# W707L.net
KiCad netlist of a schematic drawn in EAGLE
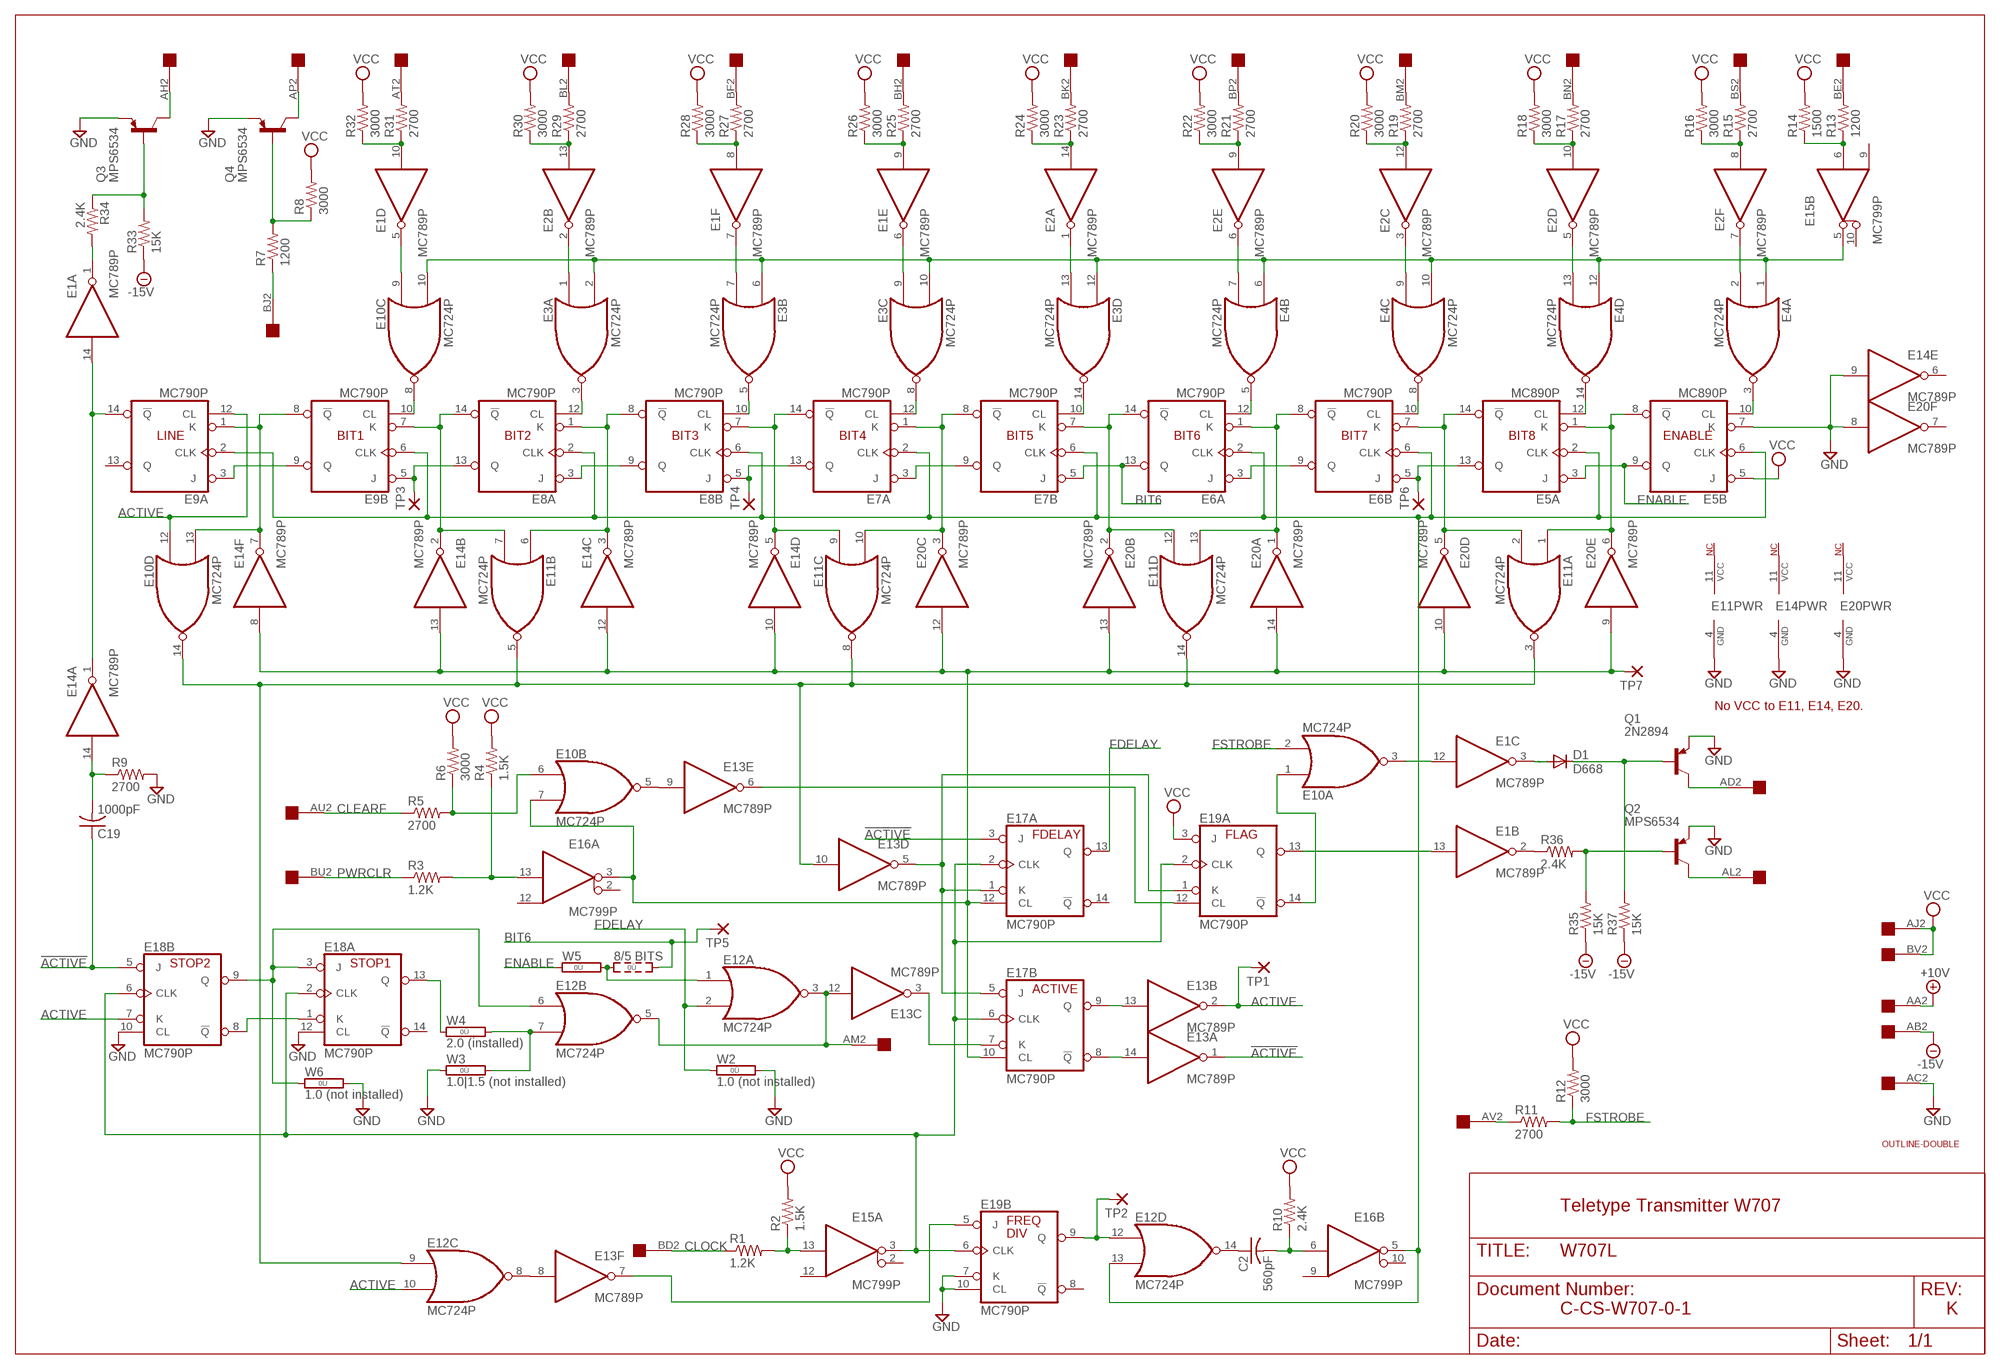
[diagram p0: schematic, sheet 1]

(export (version "E")
  (design (tool "Eeschema 10.0.6"))
  (components
    (comp (ref "C2")
      (value "560pF")
      (footprint "eagle-import:C050-025X075")
      (libsource (lib "eagle-import") (part "C-US050-025X075"))
    )
    (comp (ref "C19")
      (value "1000pF")
      (footprint "eagle-import:C050-025X075")
      (libsource (lib "eagle-import") (part "C-US050-025X075"))
    )
    (comp (ref "D1")
      (value "D668")
      (footprint "eagle-import:DO35-10")
      (libsource (lib "eagle-import") (part "1N4148DO35-10"))
    )
    (comp (ref "E1")
      (value "MC789P")
      (footprint "eagle-import:DIL14")
      (libsource (lib "eagle-import") (part "MC889P"))
    )
    (comp (ref "E2")
      (value "MC789P")
      (footprint "eagle-import:DIL14")
      (libsource (lib "eagle-import") (part "MC889P"))
    )
    (comp (ref "E3")
      (value "MC724P")
      (footprint "eagle-import:DIL14")
      (libsource (lib "eagle-import") (part "MC824P"))
    )
    (comp (ref "E4")
      (value "MC724P")
      (footprint "eagle-import:DIL14")
      (libsource (lib "eagle-import") (part "MC824P"))
    )
    (comp (ref "E5")
      (value "MC890P")
      (footprint "eagle-import:DIL14")
      (libsource (lib "eagle-import") (part "MC890P"))
    )
    (comp (ref "E6")
      (value "MC790P")
      (footprint "eagle-import:DIL14")
      (libsource (lib "eagle-import") (part "MC890P"))
    )
    (comp (ref "E7")
      (value "MC790P")
      (footprint "eagle-import:DIL14")
      (libsource (lib "eagle-import") (part "MC890P"))
    )
    (comp (ref "E8")
      (value "MC790P")
      (footprint "eagle-import:DIL14")
      (libsource (lib "eagle-import") (part "MC890P"))
    )
    (comp (ref "E9")
      (value "MC790P")
      (footprint "eagle-import:DIL14")
      (libsource (lib "eagle-import") (part "MC890P"))
    )
    (comp (ref "E10")
      (value "MC724P")
      (footprint "eagle-import:DIL14")
      (libsource (lib "eagle-import") (part "MC824P"))
    )
    (comp (ref "E11")
      (value "MC724P")
      (footprint "eagle-import:DIL14")
      (libsource (lib "eagle-import") (part "MC824P"))
    )
    (comp (ref "E12")
      (value "MC724P")
      (footprint "eagle-import:DIL14")
      (libsource (lib "eagle-import") (part "MC824P"))
    )
    (comp (ref "E13")
      (value "MC789P")
      (footprint "eagle-import:DIL14")
      (libsource (lib "eagle-import") (part "MC889P"))
    )
    (comp (ref "E14")
      (value "MC789P")
      (footprint "eagle-import:DIL14")
      (libsource (lib "eagle-import") (part "MC889P"))
    )
    (comp (ref "E15")
      (value "MC799P")
      (footprint "eagle-import:DIL14")
      (libsource (lib "eagle-import") (part "MC899P"))
    )
    (comp (ref "E16")
      (value "MC799P")
      (footprint "eagle-import:DIL14")
      (libsource (lib "eagle-import") (part "MC899P"))
    )
    (comp (ref "E17")
      (value "MC790P")
      (footprint "eagle-import:DIL14")
      (libsource (lib "eagle-import") (part "MC890P"))
    )
    (comp (ref "E18")
      (value "MC790P")
      (footprint "eagle-import:DIL14")
      (libsource (lib "eagle-import") (part "MC890P"))
    )
    (comp (ref "E19")
      (value "MC790P")
      (footprint "eagle-import:DIL14")
      (libsource (lib "eagle-import") (part "MC890P"))
    )
    (comp (ref "E20")
      (value "MC789P")
      (footprint "eagle-import:DIL14")
      (libsource (lib "eagle-import") (part "MC889P"))
    )
    (comp (ref "Q1")
      (value "2N2894")
      (footprint "eagle-import:TO39")
      (libsource (lib "eagle-import") (part "2N2904"))
    )
    (comp (ref "Q2")
      (value "MPS6534")
      (footprint "eagle-import:TO39")
      (libsource (lib "eagle-import") (part "2N2904"))
    )
    (comp (ref "Q3")
      (value "MPS6534")
      (footprint "eagle-import:TO39")
      (libsource (lib "eagle-import") (part "2N2904"))
    )
    (comp (ref "Q4")
      (value "MPS6534")
      (footprint "eagle-import:TO39")
      (libsource (lib "eagle-import") (part "2N2904"))
    )
    (comp (ref "R1")
      (value "1.2K")
      (footprint "eagle-import:0207_10")
      (libsource (lib "eagle-import") (part "R-US_0207/10"))
    )
    (comp (ref "R2")
      (value "1.5K")
      (footprint "eagle-import:0207_10")
      (libsource (lib "eagle-import") (part "R-US_0207/10"))
    )
    (comp (ref "R3")
      (value "1.2K")
      (footprint "eagle-import:0207_10")
      (libsource (lib "eagle-import") (part "R-US_0207/10"))
    )
    (comp (ref "R4")
      (value "1.5K")
      (footprint "eagle-import:0207_10")
      (libsource (lib "eagle-import") (part "R-US_0207/10"))
    )
    (comp (ref "R5")
      (value "2700")
      (footprint "eagle-import:0207_10")
      (libsource (lib "eagle-import") (part "R-US_0207/10"))
    )
    (comp (ref "R6")
      (value "3000")
      (footprint "eagle-import:0207_10")
      (libsource (lib "eagle-import") (part "R-US_0207/10"))
    )
    (comp (ref "R7")
      (value "1200")
      (footprint "eagle-import:0207_10")
      (libsource (lib "eagle-import") (part "R-US_0207/10"))
    )
    (comp (ref "R8")
      (value "3000")
      (footprint "eagle-import:0207_10")
      (libsource (lib "eagle-import") (part "R-US_0207/10"))
    )
    (comp (ref "R9")
      (value "2700")
      (footprint "eagle-import:0207_10")
      (libsource (lib "eagle-import") (part "R-US_0207/10"))
    )
    (comp (ref "R10")
      (value "2.4K")
      (footprint "eagle-import:0207_10")
      (libsource (lib "eagle-import") (part "R-US_0207/10"))
    )
    (comp (ref "R11")
      (value "2700")
      (footprint "eagle-import:0207_10")
      (libsource (lib "eagle-import") (part "R-US_0207/10"))
    )
    (comp (ref "R12")
      (value "3000")
      (footprint "eagle-import:0207_10")
      (libsource (lib "eagle-import") (part "R-US_0207/10"))
    )
    (comp (ref "R13")
      (value "1200")
      (footprint "eagle-import:0207_10")
      (libsource (lib "eagle-import") (part "R-US_0207/10"))
    )
    (comp (ref "R14")
      (value "1500")
      (footprint "eagle-import:0207_10")
      (libsource (lib "eagle-import") (part "R-US_0207/10"))
    )
    (comp (ref "R15")
      (value "2700")
      (footprint "eagle-import:0207_10")
      (libsource (lib "eagle-import") (part "R-US_0207/10"))
    )
    (comp (ref "R16")
      (value "3000")
      (footprint "eagle-import:0207_10")
      (libsource (lib "eagle-import") (part "R-US_0207/10"))
    )
    (comp (ref "R17")
      (value "2700")
      (footprint "eagle-import:0207_10")
      (libsource (lib "eagle-import") (part "R-US_0207/10"))
    )
    (comp (ref "R18")
      (value "3000")
      (footprint "eagle-import:0207_10")
      (libsource (lib "eagle-import") (part "R-US_0207/10"))
    )
    (comp (ref "R19")
      (value "2700")
      (footprint "eagle-import:0207_10")
      (libsource (lib "eagle-import") (part "R-US_0207/10"))
    )
    (comp (ref "R20")
      (value "3000")
      (footprint "eagle-import:0207_10")
      (libsource (lib "eagle-import") (part "R-US_0207/10"))
    )
    (comp (ref "R21")
      (value "2700")
      (footprint "eagle-import:0207_10")
      (libsource (lib "eagle-import") (part "R-US_0207/10"))
    )
    (comp (ref "R22")
      (value "3000")
      (footprint "eagle-import:0207_10")
      (libsource (lib "eagle-import") (part "R-US_0207/10"))
    )
    (comp (ref "R23")
      (value "2700")
      (footprint "eagle-import:0207_10")
      (libsource (lib "eagle-import") (part "R-US_0207/10"))
    )
    (comp (ref "R24")
      (value "3000")
      (footprint "eagle-import:0207_10")
      (libsource (lib "eagle-import") (part "R-US_0207/10"))
    )
    (comp (ref "R25")
      (value "2700")
      (footprint "eagle-import:0207_10")
      (libsource (lib "eagle-import") (part "R-US_0207/10"))
    )
    (comp (ref "R26")
      (value "3000")
      (footprint "eagle-import:0207_10")
      (libsource (lib "eagle-import") (part "R-US_0207/10"))
    )
    (comp (ref "R27")
      (value "2700")
      (footprint "eagle-import:0207_10")
      (libsource (lib "eagle-import") (part "R-US_0207/10"))
    )
    (comp (ref "R28")
      (value "3000")
      (footprint "eagle-import:0207_10")
      (libsource (lib "eagle-import") (part "R-US_0207/10"))
    )
    (comp (ref "R29")
      (value "2700")
      (footprint "eagle-import:0207_10")
      (libsource (lib "eagle-import") (part "R-US_0207/10"))
    )
    (comp (ref "R30")
      (value "3000")
      (footprint "eagle-import:0207_10")
      (libsource (lib "eagle-import") (part "R-US_0207/10"))
    )
    (comp (ref "R31")
      (value "2700")
      (footprint "eagle-import:0207_10")
      (libsource (lib "eagle-import") (part "R-US_0207/10"))
    )
    (comp (ref "R32")
      (value "3000")
      (footprint "eagle-import:0207_10")
      (libsource (lib "eagle-import") (part "R-US_0207/10"))
    )
    (comp (ref "R33")
      (value "15K")
      (footprint "eagle-import:0207_10")
      (libsource (lib "eagle-import") (part "R-US_0207/10"))
    )
    (comp (ref "R34")
      (value "2.4K")
      (footprint "eagle-import:0207_10")
      (libsource (lib "eagle-import") (part "R-US_0207/10"))
    )
    (comp (ref "R35")
      (value "15K")
      (footprint "eagle-import:0207_10")
      (libsource (lib "eagle-import") (part "R-US_0207/10"))
    )
    (comp (ref "R36")
      (value "2.4K")
      (footprint "eagle-import:0207_10")
      (libsource (lib "eagle-import") (part "R-US_0207/10"))
    )
    (comp (ref "R37")
      (value "15K")
      (footprint "eagle-import:0207_10")
      (libsource (lib "eagle-import") (part "R-US_0207/10"))
    )
    (comp (ref "TP1")
      (value "3,17/1,3")
      (footprint "eagle-import:3,17_1,3")
      (libsource (lib "eagle-import") (part "3,17/1,3"))
    )
    (comp (ref "TP2")
      (value "3,17/1,3")
      (footprint "eagle-import:3,17_1,3")
      (libsource (lib "eagle-import") (part "3,17/1,3"))
    )
    (comp (ref "TP3")
      (value "3,17/1,3")
      (footprint "eagle-import:3,17_1,3")
      (libsource (lib "eagle-import") (part "3,17/1,3"))
    )
    (comp (ref "TP4")
      (value "3,17/1,3")
      (footprint "eagle-import:3,17_1,3")
      (libsource (lib "eagle-import") (part "3,17/1,3"))
    )
    (comp (ref "TP5")
      (value "3,17/1,3")
      (footprint "eagle-import:3,17_1,3")
      (libsource (lib "eagle-import") (part "3,17/1,3"))
    )
    (comp (ref "TP6")
      (value "3,17/1,3")
      (footprint "eagle-import:3,17_1,3")
      (libsource (lib "eagle-import") (part "3,17/1,3"))
    )
    (comp (ref "TP7")
      (value "3,17/1,3")
      (footprint "eagle-import:3,17_1,3")
      (libsource (lib "eagle-import") (part "3,17/1,3"))
    )
    (comp (ref "U$1")
      (value "OUTLINE-DOUBLE")
      (footprint "eagle-import:DOUBLE")
      (libsource (lib "eagle-import") (part "OUTLINE-DOUBLE"))
    )
    (comp (ref "U$2")
      (value "DOUBLE")
      (footprint "eagle-import:EDGE-CON4")
      (libsource (lib "eagle-import") (part "DOUBLE"))
    )
    (comp (ref "W2")
      (value "1.0 (not installed)")
      (footprint "eagle-import:0R_10")
      (libsource (lib "eagle-import") (part "0R"))
    )
    (comp (ref "W3")
      (value "1.0|1.5 (not installed)")
      (footprint "eagle-import:0R_10")
      (libsource (lib "eagle-import") (part "0R"))
    )
    (comp (ref "W4")
      (value "2.0 (installed)")
      (footprint "eagle-import:0R_10")
      (libsource (lib "eagle-import") (part "0R"))
    )
    (comp (ref "W5")
      (value "8/5 BITS")
      (footprint "eagle-import:0R2_10")
      (libsource (lib "eagle-import") (part "0R2"))
    )
    (comp (ref "W6")
      (value "1.0 (not installed)")
      (footprint "eagle-import:0R_10")
      (libsource (lib "eagle-import") (part "0R"))
    )
  )
  (nets
    (net (code "1") (name "+10V") (class "Default")
      (node (ref "U$2") (pin "AA2") (pinfunction "1_AA2") (pintype "bidirectional"))
    )
    (net (code "2") (name "-15V") (class "Default")
      (node (ref "R33") (pin "1") (pinfunction "1_1") (pintype "passive"))
      (node (ref "R35") (pin "1") (pinfunction "1_1") (pintype "passive"))
      (node (ref "R37") (pin "1") (pinfunction "1_1") (pintype "passive"))
      (node (ref "U$2") (pin "AB2") (pinfunction "1_AB2") (pintype "bidirectional"))
    )
    (net (code "3") (name "/ACTIVE") (class "Default")
      (node (ref "E10") (pin "12") (pinfunction "I0_12") (pintype "input"))
      (node (ref "E12") (pin "10") (pinfunction "I1_10") (pintype "input"))
      (node (ref "E13") (pin "2") (pinfunction "O_2") (pintype "output"))
      (node (ref "E18") (pin "7") (pinfunction "K_7") (pintype "input"))
      (node (ref "E9") (pin "12") (pinfunction "CL_12") (pintype "input"))
      (node (ref "TP1") (pin "1") (pinfunction "P_1") (pintype "passive"))
    )
    (net (code "4") (name "/BIT6") (class "Default")
      (node (ref "E6") (pin "13") (pinfunction "Q_13") (pintype "output"))
      (node (ref "E7") (pin "5") (pinfunction "J_5") (pintype "input"))
      (node (ref "TP5") (pin "1") (pinfunction "P_1") (pintype "passive"))
      (node (ref "W5") (pin "3") (pinfunction "3_3") (pintype "passive"))
    )
    (net (code "5") (name "/CLEARF") (class "Default")
      (node (ref "R5") (pin "1") (pinfunction "1_1") (pintype "passive"))
      (node (ref "U$2") (pin "AU2") (pinfunction "1_AU2") (pintype "bidirectional"))
    )
    (net (code "6") (name "/CLOCK") (class "Default")
      (node (ref "R1") (pin "1") (pinfunction "1_1") (pintype "passive"))
      (node (ref "U$2") (pin "BD2") (pinfunction "1_BD2") (pintype "bidirectional"))
    )
    (net (code "7") (name "/ENABLE") (class "Default")
      (node (ref "E5") (pin "3") (pinfunction "J_3") (pintype "input"))
      (node (ref "E5") (pin "9") (pinfunction "Q_9") (pintype "output"))
      (node (ref "W5") (pin "1") (pinfunction "1_1") (pintype "passive"))
    )
    (net (code "8") (name "/FDELAY") (class "Default")
      (node (ref "E12") (pin "2") (pinfunction "I1_2") (pintype "input"))
      (node (ref "E17") (pin "13") (pinfunction "Q_13") (pintype "output"))
      (node (ref "W2") (pin "1") (pinfunction "1_1") (pintype "passive"))
    )
    (net (code "9") (name "/FSTROBE") (class "Default")
      (node (ref "E10") (pin "2") (pinfunction "I1_2") (pintype "input"))
      (node (ref "R11") (pin "2") (pinfunction "2_2") (pintype "passive"))
      (node (ref "R12") (pin "1") (pinfunction "1_1") (pintype "passive"))
    )
    (net (code "10") (name "/PWRCLR") (class "Default")
      (node (ref "R3") (pin "1") (pinfunction "1_1") (pintype "passive"))
      (node (ref "U$2") (pin "BU2") (pinfunction "1_BU2") (pintype "bidirectional"))
    )
    (net (code "11") (name "/~{ACTIVE}") (class "Default")
      (node (ref "C19") (pin "1") (pinfunction "1_1") (pintype "passive"))
      (node (ref "E13") (pin "1") (pinfunction "O_1") (pintype "output"))
      (node (ref "E17") (pin "3") (pinfunction "J_3") (pintype "input"))
      (node (ref "E18") (pin "5") (pinfunction "J_5") (pintype "input"))
    )
    (net (code "12") (name "GND") (class "Default")
      (node (ref "E11") (pin "4") (pinfunction "GND_4") (pintype "power_in"))
      (node (ref "E14") (pin "4") (pinfunction "GND_4") (pintype "power_in"))
      (node (ref "E14") (pin "9") (pinfunction "I_9") (pintype "input"))
      (node (ref "E18") (pin "10") (pinfunction "CL_10") (pintype "input"))
      (node (ref "E18") (pin "12") (pinfunction "CL_12") (pintype "input"))
      (node (ref "E19") (pin "10") (pinfunction "CL_10") (pintype "input"))
      (node (ref "E19") (pin "7") (pinfunction "K_7") (pintype "input"))
      (node (ref "E20") (pin "4") (pinfunction "GND_4") (pintype "power_in"))
      (node (ref "E20") (pin "8") (pinfunction "I_8") (pintype "input"))
      (node (ref "E5") (pin "7") (pinfunction "K_7") (pintype "input"))
      (node (ref "Q1") (pin "1") (pinfunction "E_1") (pintype "passive"))
      (node (ref "Q2") (pin "1") (pinfunction "E_1") (pintype "passive"))
      (node (ref "Q3") (pin "1") (pinfunction "E_1") (pintype "passive"))
      (node (ref "Q4") (pin "1") (pinfunction "E_1") (pintype "passive"))
      (node (ref "R9") (pin "2") (pinfunction "2_2") (pintype "passive"))
      (node (ref "U$2") (pin "AC2") (pinfunction "1_AC2") (pintype "bidirectional"))
      (node (ref "W2") (pin "2") (pinfunction "2_2") (pintype "passive"))
      (node (ref "W3") (pin "1") (pinfunction "1_1") (pintype "passive"))
      (node (ref "W6") (pin "2") (pinfunction "2_2") (pintype "passive"))
    )
    (net (code "13") (name "NC") (class "Default")
      (node (ref "E11") (pin "11") (pinfunction "VCC_11") (pintype "power_in"))
      (node (ref "E14") (pin "11") (pinfunction "VCC_11") (pintype "power_in"))
      (node (ref "E20") (pin "11") (pinfunction "VCC_11") (pintype "power_in"))
    )
    (net (code "14") (name "Net-(E1A-O)") (class "Default")
      (node (ref "E1") (pin "1") (pinfunction "O_1") (pintype "output"))
      (node (ref "R34") (pin "2") (pinfunction "2_2") (pintype "passive"))
    )
    (net (code "15") (name "Net-(E1B-O)") (class "Default")
      (node (ref "E1") (pin "2") (pinfunction "O_2") (pintype "output"))
      (node (ref "R36") (pin "1") (pinfunction "1_1") (pintype "passive"))
    )
    (net (code "16") (name "Net-(E1C-O)") (class "Default")
      (node (ref "D1") (pin "A") (pinfunction "A_A") (pintype "passive"))
      (node (ref "E1") (pin "3") (pinfunction "O_3") (pintype "output"))
    )
    (net (code "17") (name "Net-(E1D-I)") (class "Default")
      (node (ref "E1") (pin "10") (pinfunction "I_10") (pintype "input"))
      (node (ref "R31") (pin "1") (pinfunction "1_1") (pintype "passive"))
      (node (ref "R32") (pin "1") (pinfunction "1_1") (pintype "passive"))
    )
    (net (code "18") (name "Net-(E1E-I)") (class "Default")
      (node (ref "E1") (pin "9") (pinfunction "I_9") (pintype "input"))
      (node (ref "R25") (pin "1") (pinfunction "1_1") (pintype "passive"))
      (node (ref "R26") (pin "1") (pinfunction "1_1") (pintype "passive"))
    )
    (net (code "19") (name "Net-(E1E-O)") (class "Default")
      (node (ref "E1") (pin "6") (pinfunction "O_6") (pintype "output"))
      (node (ref "E3") (pin "9") (pinfunction "I0_9") (pintype "input"))
    )
    (net (code "20") (name "Net-(E1F-I)") (class "Default")
      (node (ref "E1") (pin "8") (pinfunction "I_8") (pintype "input"))
      (node (ref "R27") (pin "1") (pinfunction "1_1") (pintype "passive"))
      (node (ref "R28") (pin "1") (pinfunction "1_1") (pintype "passive"))
    )
    (net (code "21") (name "Net-(E1F-O)") (class "Default")
      (node (ref "E1") (pin "7") (pinfunction "O_7") (pintype "output"))
      (node (ref "E3") (pin "7") (pinfunction "I1_7") (pintype "input"))
    )
    (net (code "22") (name "Net-(E2A-I)") (class "Default")
      (node (ref "E2") (pin "14") (pinfunction "I_14") (pintype "input"))
      (node (ref "R23") (pin "1") (pinfunction "1_1") (pintype "passive"))
      (node (ref "R24") (pin "1") (pinfunction "1_1") (pintype "passive"))
    )
    (net (code "23") (name "Net-(E2A-O)") (class "Default")
      (node (ref "E2") (pin "1") (pinfunction "O_1") (pintype "output"))
      (node (ref "E3") (pin "13") (pinfunction "I1_13") (pintype "input"))
    )
    (net (code "24") (name "Net-(E2B-I)") (class "Default")
      (node (ref "E2") (pin "13") (pinfunction "I_13") (pintype "input"))
      (node (ref "R29") (pin "1") (pinfunction "1_1") (pintype "passive"))
      (node (ref "R30") (pin "1") (pinfunction "1_1") (pintype "passive"))
    )
    (net (code "25") (name "Net-(E2B-O)") (class "Default")
      (node (ref "E2") (pin "2") (pinfunction "O_2") (pintype "output"))
      (node (ref "E3") (pin "1") (pinfunction "I0_1") (pintype "input"))
    )
    (net (code "26") (name "Net-(E2C-I)") (class "Default")
      (node (ref "E2") (pin "12") (pinfunction "I_12") (pintype "input"))
      (node (ref "R19") (pin "1") (pinfunction "1_1") (pintype "passive"))
      (node (ref "R20") (pin "1") (pinfunction "1_1") (pintype "passive"))
    )
    (net (code "27") (name "Net-(E2C-O)") (class "Default")
      (node (ref "E2") (pin "3") (pinfunction "O_3") (pintype "output"))
      (node (ref "E4") (pin "9") (pinfunction "I0_9") (pintype "input"))
    )
    (net (code "28") (name "Net-(E2D-I)") (class "Default")
      (node (ref "E2") (pin "10") (pinfunction "I_10") (pintype "input"))
      (node (ref "R17") (pin "1") (pinfunction "1_1") (pintype "passive"))
      (node (ref "R18") (pin "1") (pinfunction "1_1") (pintype "passive"))
    )
    (net (code "29") (name "Net-(E2D-O)") (class "Default")
      (node (ref "E2") (pin "5") (pinfunction "O_5") (pintype "output"))
      (node (ref "E4") (pin "13") (pinfunction "I1_13") (pintype "input"))
    )
    (net (code "30") (name "Net-(E2E-I)") (class "Default")
      (node (ref "E2") (pin "9") (pinfunction "I_9") (pintype "input"))
      (node (ref "R21") (pin "1") (pinfunction "1_1") (pintype "passive"))
      (node (ref "R22") (pin "1") (pinfunction "1_1") (pintype "passive"))
    )
    (net (code "31") (name "Net-(E2E-O)") (class "Default")
      (node (ref "E2") (pin "6") (pinfunction "O_6") (pintype "output"))
      (node (ref "E4") (pin "7") (pinfunction "I1_7") (pintype "input"))
    )
    (net (code "32") (name "Net-(E2F-I)") (class "Default")
      (node (ref "E2") (pin "8") (pinfunction "I_8") (pintype "input"))
      (node (ref "R15") (pin "1") (pinfunction "1_1") (pintype "passive"))
      (node (ref "R16") (pin "1") (pinfunction "1_1") (pintype "passive"))
    )
    (net (code "33") (name "Net-(E2F-O)") (class "Default")
      (node (ref "E2") (pin "7") (pinfunction "O_7") (pintype "output"))
      (node (ref "E4") (pin "2") (pinfunction "I1_2") (pintype "input"))
    )
    (net (code "34") (name "Net-(E3A-O)") (class "Default")
      (node (ref "E3") (pin "3") (pinfunction "O_3") (pintype "output"))
      (node (ref "E8") (pin "12") (pinfunction "CL_12") (pintype "input"))
    )
    (net (code "35") (name "Net-(E3B-O)") (class "Default")
      (node (ref "E3") (pin "5") (pinfunction "O_5") (pintype "output"))
      (node (ref "E8") (pin "10") (pinfunction "CL_10") (pintype "input"))
    )
    (net (code "36") (name "Net-(E3C-O)") (class "Default")
      (node (ref "E3") (pin "8") (pinfunction "O_8") (pintype "output"))
      (node (ref "E7") (pin "12") (pinfunction "CL_12") (pintype "input"))
    )
    (net (code "37") (name "Net-(E3D-O)") (class "Default")
      (node (ref "E3") (pin "14") (pinfunction "O_14") (pintype "output"))
      (node (ref "E7") (pin "10") (pinfunction "CL_10") (pintype "input"))
    )
    (net (code "38") (name "Net-(E4A-O)") (class "Default")
      (node (ref "E4") (pin "3") (pinfunction "O_3") (pintype "output"))
      (node (ref "E5") (pin "10") (pinfunction "CL_10") (pintype "input"))
    )
    (net (code "39") (name "Net-(E4B-O)") (class "Default")
      (node (ref "E4") (pin "5") (pinfunction "O_5") (pintype "output"))
      (node (ref "E6") (pin "12") (pinfunction "CL_12") (pintype "input"))
    )
    (net (code "40") (name "Net-(E4C-O)") (class "Default")
      (node (ref "E4") (pin "8") (pinfunction "O_8") (pintype "output"))
      (node (ref "E6") (pin "10") (pinfunction "CL_10") (pintype "input"))
    )
    (net (code "41") (name "Net-(E4D-O)") (class "Default")
      (node (ref "E4") (pin "14") (pinfunction "O_14") (pintype "output"))
      (node (ref "E5") (pin "12") (pinfunction "CL_12") (pintype "input"))
    )
    (net (code "42") (name "Net-(E5A-Q)") (class "Default")
      (node (ref "E5") (pin "13") (pinfunction "Q_13") (pintype "output"))
      (node (ref "E6") (pin "5") (pinfunction "J_5") (pintype "input"))
      (node (ref "TP6") (pin "1") (pinfunction "P_1") (pintype "passive"))
    )
    (net (code "43") (name "Net-(E6A-J)") (class "Default")
      (node (ref "E6") (pin "3") (pinfunction "J_3") (pintype "input"))
      (node (ref "E6") (pin "9") (pinfunction "Q_9") (pintype "output"))
    )
    (net (code "44") (name "Net-(E7A-J)") (class "Default")
      (node (ref "E7") (pin "3") (pinfunction "J_3") (pintype "input"))
      (node (ref "E7") (pin "9") (pinfunction "Q_9") (pintype "output"))
    )
    (net (code "45") (name "Net-(E7A-Q)") (class "Default")
      (node (ref "E7") (pin "13") (pinfunction "Q_13") (pintype "output"))
      (node (ref "E8") (pin "5") (pinfunction "J_5") (pintype "input"))
      (node (ref "TP4") (pin "1") (pinfunction "P_1") (pintype "passive"))
    )
    (net (code "46") (name "Net-(E8A-J)") (class "Default")
      (node (ref "E8") (pin "3") (pinfunction "J_3") (pintype "input"))
      (node (ref "E8") (pin "9") (pinfunction "Q_9") (pintype "output"))
    )
    (net (code "47") (name "Net-(E8A-Q)") (class "Default")
      (node (ref "E8") (pin "13") (pinfunction "Q_13") (pintype "output"))
      (node (ref "E9") (pin "5") (pinfunction "J_5") (pintype "input"))
      (node (ref "TP3") (pin "1") (pinfunction "P_1") (pintype "passive"))
    )
    (net (code "48") (name "Net-(E9A-J)") (class "Default")
      (node (ref "E9") (pin "3") (pinfunction "J_3") (pintype "input"))
      (node (ref "E9") (pin "9") (pinfunction "Q_9") (pintype "output"))
    )
    (net (code "49") (name "Net-(E10A-I0)") (class "Default")
      (node (ref "E10") (pin "1") (pinfunction "I0_1") (pintype "input"))
      (node (ref "E19") (pin "14") (pinfunction "~{Q}_14") (pintype "output"))
    )
    (net (code "50") (name "Net-(E10A-O)") (class "Default")
      (node (ref "E1") (pin "12") (pinfunction "I_12") (pintype "input"))
      (node (ref "E10") (pin "3") (pinfunction "O_3") (pintype "output"))
    )
    (net (code "51") (name "Net-(E10B-I0)") (class "Default")
      (node (ref "E10") (pin "6") (pinfunction "I0_6") (pintype "input"))
      (node (ref "R5") (pin "2") (pinfunction "2_2") (pintype "passive"))
      (node (ref "R6") (pin "1") (pinfunction "1_1") (pintype "passive"))
    )
    (net (code "52") (name "Net-(E10B-I1)") (class "Default")
      (node (ref "E10") (pin "7") (pinfunction "I1_7") (pintype "input"))
      (node (ref "E14") (pin "10") (pinfunction "I_10") (pintype "input"))
      (node (ref "E14") (pin "12") (pinfunction "I_12") (pintype "input"))
      (node (ref "E14") (pin "13") (pinfunction "I_13") (pintype "input"))
      (node (ref "E14") (pin "8") (pinfunction "I_8") (pintype "input"))
      (node (ref "E16") (pin "3") (pinfunction "O_3") (pintype "output"))
      (node (ref "E17") (pin "10") (pinfunction "CL_10") (pintype "input"))
      (node (ref "E17") (pin "12") (pinfunction "CL_12") (pintype "input"))
      (node (ref "E20") (pin "10") (pinfunction "I_10") (pintype "input"))
      (node (ref "E20") (pin "12") (pinfunction "I_12") (pintype "input"))
      (node (ref "E20") (pin "13") (pinfunction "I_13") (pintype "input"))
      (node (ref "E20") (pin "14") (pinfunction "I_14") (pintype "input"))
      (node (ref "E20") (pin "9") (pinfunction "I_9") (pintype "input"))
      (node (ref "TP7") (pin "1") (pinfunction "P_1") (pintype "passive"))
    )
    (net (code "53") (name "Net-(E10B-O)") (class "Default")
      (node (ref "E10") (pin "5") (pinfunction "O_5") (pintype "output"))
      (node (ref "E13") (pin "9") (pinfunction "I_9") (pintype "input"))
    )
    (net (code "54") (name "Net-(E10C-I0)") (class "Default")
      (node (ref "E1") (pin "5") (pinfunction "O_5") (pintype "output"))
      (node (ref "E10") (pin "9") (pinfunction "I0_9") (pintype "input"))
    )
    (net (code "55") (name "Net-(E10C-I1)") (class "Default")
      (node (ref "E10") (pin "10") (pinfunction "I1_10") (pintype "input"))
      (node (ref "E15") (pin "5") (pinfunction "O_5") (pintype "output"))
      (node (ref "E3") (pin "10") (pinfunction "I1_10") (pintype "input"))
      (node (ref "E3") (pin "12") (pinfunction "I0_12") (pintype "input"))
      (node (ref "E3") (pin "2") (pinfunction "I1_2") (pintype "input"))
      (node (ref "E3") (pin "6") (pinfunction "I0_6") (pintype "input"))
      (node (ref "E4") (pin "1") (pinfunction "I0_1") (pintype "input"))
      (node (ref "E4") (pin "10") (pinfunction "I1_10") (pintype "input"))
      (node (ref "E4") (pin "12") (pinfunction "I0_12") (pintype "input"))
      (node (ref "E4") (pin "6") (pinfunction "I0_6") (pintype "input"))
    )
    (net (code "56") (name "Net-(E10C-O)") (class "Default")
      (node (ref "E10") (pin "8") (pinfunction "O_8") (pintype "output"))
      (node (ref "E9") (pin "10") (pinfunction "CL_10") (pintype "input"))
    )
    (net (code "57") (name "Net-(E10D-I1)") (class "Default")
      (node (ref "E10") (pin "13") (pinfunction "I1_13") (pintype "input"))
      (node (ref "E14") (pin "7") (pinfunction "O_7") (pintype "output"))
      (node (ref "E9") (pin "1") (pinfunction "K_1") (pintype "input"))
      (node (ref "E9") (pin "8") (pinfunction "~{Q}_8") (pintype "output"))
    )
    (net (code "58") (name "Net-(E10D-O)") (class "Default")
      (node (ref "E10") (pin "14") (pinfunction "O_14") (pintype "output"))
      (node (ref "E11") (pin "14") (pinfunction "O_14") (pintype "output"))
      (node (ref "E11") (pin "3") (pinfunction "O_3") (pintype "output"))
      (node (ref "E11") (pin "5") (pinfunction "O_5") (pintype "output"))
      (node (ref "E11") (pin "8") (pinfunction "O_8") (pintype "output"))
      (node (ref "E12") (pin "9") (pinfunction "I0_9") (pintype "input"))
      (node (ref "E13") (pin "10") (pinfunction "I_10") (pintype "input"))
    )
    (net (code "59") (name "Net-(E11A-I0)") (class "Default")
      (node (ref "E11") (pin "1") (pinfunction "I0_1") (pintype "input"))
      (node (ref "E20") (pin "6") (pinfunction "O_6") (pintype "output"))
      (node (ref "E5") (pin "1") (pinfunction "K_1") (pintype "input"))
      (node (ref "E5") (pin "8") (pinfunction "~{Q}_8") (pintype "output"))
    )
    (net (code "60") (name "Net-(E11A-I1)") (class "Default")
      (node (ref "E11") (pin "2") (pinfunction "I1_2") (pintype "input"))
      (node (ref "E20") (pin "5") (pinfunction "O_5") (pintype "output"))
      (node (ref "E5") (pin "14") (pinfunction "~{Q}_14") (pintype "output"))
      (node (ref "E6") (pin "7") (pinfunction "K_7") (pintype "input"))
    )
    (net (code "61") (name "Net-(E11B-I0)") (class "Default")
      (node (ref "E11") (pin "6") (pinfunction "I0_6") (pintype "input"))
      (node (ref "E14") (pin "3") (pinfunction "O_3") (pintype "output"))
      (node (ref "E8") (pin "1") (pinfunction "K_1") (pintype "input"))
      (node (ref "E8") (pin "8") (pinfunction "~{Q}_8") (pintype "output"))
    )
    (net (code "62") (name "Net-(E11B-I1)") (class "Default")
      (node (ref "E11") (pin "7") (pinfunction "I1_7") (pintype "input"))
      (node (ref "E14") (pin "2") (pinfunction "O_2") (pintype "output"))
      (node (ref "E8") (pin "14") (pinfunction "~{Q}_14") (pintype "output"))
      (node (ref "E9") (pin "7") (pinfunction "K_7") (pintype "input"))
    )
    (net (code "63") (name "Net-(E11C-I0)") (class "Default")
      (node (ref "E11") (pin "9") (pinfunction "I0_9") (pintype "input"))
      (node (ref "E14") (pin "5") (pinfunction "O_5") (pintype "output"))
      (node (ref "E7") (pin "14") (pinfunction "~{Q}_14") (pintype "output"))
      (node (ref "E8") (pin "7") (pinfunction "K_7") (pintype "input"))
    )
    (net (code "64") (name "Net-(E11C-I1)") (class "Default")
      (node (ref "E11") (pin "10") (pinfunction "I1_10") (pintype "input"))
      (node (ref "E20") (pin "3") (pinfunction "O_3") (pintype "output"))
      (node (ref "E7") (pin "1") (pinfunction "K_1") (pintype "input"))
      (node (ref "E7") (pin "8") (pinfunction "~{Q}_8") (pintype "output"))
    )
    (net (code "65") (name "Net-(E11D-I0)") (class "Default")
      (node (ref "E11") (pin "12") (pinfunction "I0_12") (pintype "input"))
      (node (ref "E20") (pin "2") (pinfunction "O_2") (pintype "output"))
      (node (ref "E6") (pin "14") (pinfunction "~{Q}_14") (pintype "output"))
      (node (ref "E7") (pin "7") (pinfunction "K_7") (pintype "input"))
    )
    (net (code "66") (name "Net-(E11D-I1)") (class "Default")
      (node (ref "E11") (pin "13") (pinfunction "I1_13") (pintype "input"))
      (node (ref "E20") (pin "1") (pinfunction "O_1") (pintype "output"))
      (node (ref "E6") (pin "1") (pinfunction "K_1") (pintype "input"))
      (node (ref "E6") (pin "8") (pinfunction "~{Q}_8") (pintype "output"))
    )
    (net (code "67") (name "Net-(E12A-I0)") (class "Default")
      (node (ref "E12") (pin "1") (pinfunction "I0_1") (pintype "input"))
      (node (ref "W5") (pin "2") (pinfunction "2_2") (pintype "passive"))
    )
    (net (code "68") (name "Net-(E12A-O)") (class "Default")
      (node (ref "E12") (pin "3") (pinfunction "O_3") (pintype "output"))
      (node (ref "E12") (pin "5") (pinfunction "O_5") (pintype "output"))
      (node (ref "E13") (pin "12") (pinfunction "I_12") (pintype "input"))
      (node (ref "U$2") (pin "AM2") (pinfunction "1_AM2") (pintype "bidirectional"))
    )
    (net (code "69") (name "Net-(E12B-I0)") (class "Default")
      (node (ref "E12") (pin "6") (pinfunction "I0_6") (pintype "input"))
      (node (ref "E18") (pin "3") (pinfunction "J_3") (pintype "input"))
      (node (ref "E18") (pin "9") (pinfunction "Q_9") (pintype "output"))
      (node (ref "W6") (pin "1") (pinfunction "1_1") (pintype "passive"))
    )
    (net (code "70") (name "Net-(E12B-I1)") (class "Default")
      (node (ref "E12") (pin "7") (pinfunction "I1_7") (pintype "input"))
      (node (ref "W3") (pin "2") (pinfunction "2_2") (pintype "passive"))
      (node (ref "W4") (pin "2") (pinfunction "2_2") (pintype "passive"))
    )
    (net (code "71") (name "Net-(E12C-O)") (class "Default")
      (node (ref "E12") (pin "8") (pinfunction "O_8") (pintype "output"))
      (node (ref "E13") (pin "8") (pinfunction "I_8") (pintype "input"))
    )
    (net (code "72") (name "Net-(E12D-I0)") (class "Default")
      (node (ref "E12") (pin "12") (pinfunction "I0_12") (pintype "input"))
      (node (ref "E19") (pin "9") (pinfunction "Q_9") (pintype "output"))
      (node (ref "TP2") (pin "1") (pinfunction "P_1") (pintype "passive"))
    )
    (net (code "73") (name "Net-(E12D-I1)") (class "Default")
      (node (ref "E12") (pin "13") (pinfunction "I1_13") (pintype "input"))
      (node (ref "E16") (pin "5") (pinfunction "O_5") (pintype "output"))
      (node (ref "E5") (pin "2") (pinfunction "CLK_2") (pintype "input"))
      (node (ref "E5") (pin "6") (pinfunction "CLK_6") (pintype "input"))
      (node (ref "E6") (pin "2") (pinfunction "CLK_2") (pintype "input"))
      (node (ref "E6") (pin "6") (pinfunction "CLK_6") (pintype "input"))
      (node (ref "E7") (pin "2") (pinfunction "CLK_2") (pintype "input"))
      (node (ref "E7") (pin "6") (pinfunction "CLK_6") (pintype "input"))
      (node (ref "E8") (pin "2") (pinfunction "CLK_2") (pintype "input"))
      (node (ref "E8") (pin "6") (pinfunction "CLK_6") (pintype "input"))
      (node (ref "E9") (pin "2") (pinfunction "CLK_2") (pintype "input"))
      (node (ref "E9") (pin "6") (pinfunction "CLK_6") (pintype "input"))
    )
    (net (code "74") (name "Net-(E12D-O)") (class "Default")
      (node (ref "C2") (pin "1") (pinfunction "1_1") (pintype "passive"))
      (node (ref "E12") (pin "14") (pinfunction "O_14") (pintype "output"))
    )
    (net (code "75") (name "Net-(E13A-I)") (class "Default")
      (node (ref "E13") (pin "14") (pinfunction "I_14") (pintype "input"))
      (node (ref "E17") (pin "8") (pinfunction "~{Q}_8") (pintype "output"))
    )
    (net (code "76") (name "Net-(E13B-I)") (class "Default")
      (node (ref "E13") (pin "13") (pinfunction "I_13") (pintype "input"))
      (node (ref "E17") (pin "9") (pinfunction "Q_9") (pintype "output"))
    )
    (net (code "77") (name "Net-(E13C-O)") (class "Default")
      (node (ref "E13") (pin "3") (pinfunction "O_3") (pintype "output"))
      (node (ref "E17") (pin "7") (pinfunction "K_7") (pintype "input"))
    )
    (net (code "78") (name "Net-(E13D-O)") (class "Default")
      (node (ref "E13") (pin "5") (pinfunction "O_5") (pintype "output"))
      (node (ref "E17") (pin "1") (pinfunction "K_1") (pintype "input"))
      (node (ref "E17") (pin "5") (pinfunction "J_5") (pintype "input"))
      (node (ref "E19") (pin "1") (pinfunction "K_1") (pintype "input"))
    )
    (net (code "79") (name "Net-(E13E-O)") (class "Default")
      (node (ref "E13") (pin "6") (pinfunction "O_6") (pintype "output"))
      (node (ref "E19") (pin "12") (pinfunction "CL_12") (pintype "input"))
    )
    (net (code "80") (name "Net-(E13F-O)") (class "Default")
      (node (ref "E13") (pin "7") (pinfunction "O_7") (pintype "output"))
      (node (ref "E19") (pin "5") (pinfunction "J_5") (pintype "input"))
    )
    (net (code "81") (name "Net-(E14A-I)") (class "Default")
      (node (ref "C19") (pin "2") (pinfunction "2_2") (pintype "passive"))
      (node (ref "E14") (pin "14") (pinfunction "I_14") (pintype "input"))
      (node (ref "R9") (pin "1") (pinfunction "1_1") (pintype "passive"))
    )
    (net (code "82") (name "Net-(E14A-O)") (class "Default")
      (node (ref "E1") (pin "14") (pinfunction "I_14") (pintype "input"))
      (node (ref "E14") (pin "1") (pinfunction "O_1") (pintype "output"))
      (node (ref "E9") (pin "14") (pinfunction "~{Q}_14") (pintype "output"))
    )
    (net (code "83") (name "Net-(E15A-I)") (class "Default")
      (node (ref "E15") (pin "13") (pinfunction "I_13") (pintype "input"))
      (node (ref "R1") (pin "2") (pinfunction "2_2") (pintype "passive"))
      (node (ref "R2") (pin "1") (pinfunction "1_1") (pintype "passive"))
    )
    (net (code "84") (name "Net-(E15A-O)") (class "Default")
      (node (ref "E15") (pin "3") (pinfunction "O_3") (pintype "output"))
      (node (ref "E17") (pin "2") (pinfunction "CLK_2") (pintype "input"))
      (node (ref "E17") (pin "6") (pinfunction "CLK_6") (pintype "input"))
      (node (ref "E18") (pin "2") (pinfunction "CLK_2") (pintype "input"))
      (node (ref "E18") (pin "6") (pinfunction "CLK_6") (pintype "input"))
      (node (ref "E19") (pin "2") (pinfunction "CLK_2") (pintype "input"))
      (node (ref "E19") (pin "6") (pinfunction "CLK_6") (pintype "input"))
    )
    (net (code "85") (name "Net-(E15B-I)") (class "Default")
      (node (ref "E15") (pin "6") (pinfunction "I_6") (pintype "input"))
      (node (ref "R13") (pin "1") (pinfunction "1_1") (pintype "passive"))
      (node (ref "R14") (pin "1") (pinfunction "1_1") (pintype "passive"))
    )
    (net (code "86") (name "Net-(E16A-I)") (class "Default")
      (node (ref "E16") (pin "13") (pinfunction "I_13") (pintype "input"))
      (node (ref "R3") (pin "2") (pinfunction "2_2") (pintype "passive"))
      (node (ref "R4") (pin "1") (pinfunction "1_1") (pintype "passive"))
    )
    (net (code "87") (name "Net-(E16B-I)") (class "Default")
      (node (ref "C2") (pin "2") (pinfunction "2_2") (pintype "passive"))
      (node (ref "E16") (pin "6") (pinfunction "I_6") (pintype "input"))
      (node (ref "R10") (pin "1") (pinfunction "1_1") (pintype "passive"))
    )
    (net (code "88") (name "Net-(E18A-K)") (class "Default")
      (node (ref "E18") (pin "1") (pinfunction "K_1") (pintype "input"))
      (node (ref "E18") (pin "8") (pinfunction "~{Q}_8") (pintype "output"))
    )
    (net (code "89") (name "Net-(E18A-Q)") (class "Default")
      (node (ref "E18") (pin "13") (pinfunction "Q_13") (pintype "output"))
      (node (ref "W4") (pin "1") (pinfunction "1_1") (pintype "passive"))
    )
    (net (code "90") (name "Net-(E19A-Q)") (class "Default")
      (node (ref "E1") (pin "13") (pinfunction "I_13") (pintype "input"))
      (node (ref "E19") (pin "13") (pinfunction "Q_13") (pintype "output"))
    )
    (net (code "91") (name "Net-(Q1-B)") (class "Default")
      (node (ref "D1") (pin "C") (pinfunction "C_C") (pintype "passive"))
      (node (ref "Q1") (pin "2") (pinfunction "B_2") (pintype "passive"))
      (node (ref "R37") (pin "2") (pinfunction "2_2") (pintype "passive"))
    )
    (net (code "92") (name "Net-(Q1-C)") (class "Default")
      (node (ref "Q1") (pin "3") (pinfunction "C_3") (pintype "passive"))
      (node (ref "U$2") (pin "AD2") (pinfunction "1_AD2") (pintype "bidirectional"))
    )
    (net (code "93") (name "Net-(Q2-B)") (class "Default")
      (node (ref "Q2") (pin "2") (pinfunction "B_2") (pintype "passive"))
      (node (ref "R35") (pin "2") (pinfunction "2_2") (pintype "passive"))
      (node (ref "R36") (pin "2") (pinfunction "2_2") (pintype "passive"))
    )
    (net (code "94") (name "Net-(Q2-C)") (class "Default")
      (node (ref "Q2") (pin "3") (pinfunction "C_3") (pintype "passive"))
      (node (ref "U$2") (pin "AL2") (pinfunction "1_AL2") (pintype "bidirectional"))
    )
    (net (code "95") (name "Net-(Q3-B)") (class "Default")
      (node (ref "Q3") (pin "2") (pinfunction "B_2") (pintype "passive"))
      (node (ref "R33") (pin "2") (pinfunction "2_2") (pintype "passive"))
      (node (ref "R34") (pin "1") (pinfunction "1_1") (pintype "passive"))
    )
    (net (code "96") (name "Net-(Q3-C)") (class "Default")
      (node (ref "Q3") (pin "3") (pinfunction "C_3") (pintype "passive"))
      (node (ref "U$2") (pin "AH2") (pinfunction "1_AH2") (pintype "bidirectional"))
    )
    (net (code "97") (name "Net-(Q4-B)") (class "Default")
      (node (ref "Q4") (pin "2") (pinfunction "B_2") (pintype "passive"))
      (node (ref "R7") (pin "2") (pinfunction "2_2") (pintype "passive"))
      (node (ref "R8") (pin "1") (pinfunction "1_1") (pintype "passive"))
    )
    (net (code "98") (name "Net-(Q4-C)") (class "Default")
      (node (ref "Q4") (pin "3") (pinfunction "C_3") (pintype "passive"))
      (node (ref "U$2") (pin "AP2") (pinfunction "1_AP2") (pintype "bidirectional"))
    )
    (net (code "99") (name "Net-(U$2AF-1)") (class "Default")
      (node (ref "R31") (pin "2") (pinfunction "2_2") (pintype "passive"))
      (node (ref "U$2") (pin "AT2") (pinfunction "1_AT2") (pintype "bidirectional"))
    )
    (net (code "100") (name "Net-(U$2AJ-1)") (class "Default")
      (node (ref "R11") (pin "1") (pinfunction "1_1") (pintype "passive"))
      (node (ref "U$2") (pin "AV2") (pinfunction "1_AV2") (pintype "bidirectional"))
    )
    (net (code "101") (name "Net-(U$2AT-1)") (class "Default")
      (node (ref "R13") (pin "2") (pinfunction "2_2") (pintype "passive"))
      (node (ref "U$2") (pin "BE2") (pinfunction "1_BE2") (pintype "bidirectional"))
    )
    (net (code "102") (name "Net-(U$2AV-1)") (class "Default")
      (node (ref "R27") (pin "2") (pinfunction "2_2") (pintype "passive"))
      (node (ref "U$2") (pin "BF2") (pinfunction "1_BF2") (pintype "bidirectional"))
    )
    (net (code "103") (name "Net-(U$2AX-1)") (class "Default")
      (node (ref "R25") (pin "2") (pinfunction "2_2") (pintype "passive"))
      (node (ref "U$2") (pin "BH2") (pinfunction "1_BH2") (pintype "bidirectional"))
    )
    (net (code "104") (name "Net-(U$2AZ-1)") (class "Default")
      (node (ref "R7") (pin "1") (pinfunction "1_1") (pintype "passive"))
      (node (ref "U$2") (pin "BJ2") (pinfunction "1_BJ2") (pintype "bidirectional"))
    )
    (net (code "105") (name "Net-(U$2BB-1)") (class "Default")
      (node (ref "R23") (pin "2") (pinfunction "2_2") (pintype "passive"))
      (node (ref "U$2") (pin "BK2") (pinfunction "1_BK2") (pintype "bidirectional"))
    )
    (net (code "106") (name "Net-(U$2BD-1)") (class "Default")
      (node (ref "R29") (pin "2") (pinfunction "2_2") (pintype "passive"))
      (node (ref "U$2") (pin "BL2") (pinfunction "1_BL2") (pintype "bidirectional"))
    )
    (net (code "107") (name "Net-(U$2BF-1)") (class "Default")
      (node (ref "R19") (pin "2") (pinfunction "2_2") (pintype "passive"))
      (node (ref "U$2") (pin "BM2") (pinfunction "1_BM2") (pintype "bidirectional"))
    )
    (net (code "108") (name "Net-(U$2BH-1)") (class "Default")
      (node (ref "R17") (pin "2") (pinfunction "2_2") (pintype "passive"))
      (node (ref "U$2") (pin "BN2") (pinfunction "1_BN2") (pintype "bidirectional"))
    )
    (net (code "109") (name "Net-(U$2BJ-1)") (class "Default")
      (node (ref "R21") (pin "2") (pinfunction "2_2") (pintype "passive"))
      (node (ref "U$2") (pin "BP2") (pinfunction "1_BP2") (pintype "bidirectional"))
    )
    (net (code "110") (name "Net-(U$2BN-1)") (class "Default")
      (node (ref "R15") (pin "2") (pinfunction "2_2") (pintype "passive"))
      (node (ref "U$2") (pin "BS2") (pinfunction "1_BS2") (pintype "bidirectional"))
    )
    (net (code "111") (name "VCC") (class "Default")
      (node (ref "E19") (pin "3") (pinfunction "J_3") (pintype "input"))
      (node (ref "E5") (pin "5") (pinfunction "J_5") (pintype "input"))
      (node (ref "R10") (pin "2") (pinfunction "2_2") (pintype "passive"))
      (node (ref "R12") (pin "2") (pinfunction "2_2") (pintype "passive"))
      (node (ref "R14") (pin "2") (pinfunction "2_2") (pintype "passive"))
      (node (ref "R16") (pin "2") (pinfunction "2_2") (pintype "passive"))
      (node (ref "R18") (pin "2") (pinfunction "2_2") (pintype "passive"))
      (node (ref "R2") (pin "2") (pinfunction "2_2") (pintype "passive"))
      (node (ref "R20") (pin "2") (pinfunction "2_2") (pintype "passive"))
      (node (ref "R22") (pin "2") (pinfunction "2_2") (pintype "passive"))
      (node (ref "R24") (pin "2") (pinfunction "2_2") (pintype "passive"))
      (node (ref "R26") (pin "2") (pinfunction "2_2") (pintype "passive"))
      (node (ref "R28") (pin "2") (pinfunction "2_2") (pintype "passive"))
      (node (ref "R30") (pin "2") (pinfunction "2_2") (pintype "passive"))
      (node (ref "R32") (pin "2") (pinfunction "2_2") (pintype "passive"))
      (node (ref "R4") (pin "2") (pinfunction "2_2") (pintype "passive"))
      (node (ref "R6") (pin "2") (pinfunction "2_2") (pintype "passive"))
      (node (ref "R8") (pin "2") (pinfunction "2_2") (pintype "passive"))
      (node (ref "U$2") (pin "AJ2") (pinfunction "1_AJ2") (pintype "bidirectional"))
      (node (ref "U$2") (pin "BV2") (pinfunction "1_BV2") (pintype "bidirectional"))
    )
    (net (code "112") (name "unconnected-(E9A-Q-Pad13)") (class "Default")
      (node (ref "E9") (pin "13") (pinfunction "Q_13") (pintype "output"))
    )
    (net (code "113") (name "unconnected-(E14E-O-Pad6)") (class "Default")
      (node (ref "E14") (pin "6") (pinfunction "O_6") (pintype "output"))
    )
    (net (code "114") (name "unconnected-(E15A-E-Pad2)") (class "Default")
      (node (ref "E15") (pin "2") (pinfunction "E_2") (pintype "output"))
    )
    (net (code "115") (name "unconnected-(E15A-R-Pad12)") (class "Default")
      (node (ref "E15") (pin "12") (pinfunction "R_12") (pintype "passive"))
    )
    (net (code "116") (name "unconnected-(E15B-E-Pad10)") (class "Default")
      (node (ref "E15") (pin "10") (pinfunction "E_10") (pintype "output"))
    )
    (net (code "117") (name "unconnected-(E15B-R-Pad9)") (class "Default")
      (node (ref "E15") (pin "9") (pinfunction "R_9") (pintype "passive"))
    )
    (net (code "118") (name "unconnected-(E16A-E-Pad2)") (class "Default")
      (node (ref "E16") (pin "2") (pinfunction "E_2") (pintype "output"))
    )
    (net (code "119") (name "unconnected-(E16A-R-Pad12)") (class "Default")
      (node (ref "E16") (pin "12") (pinfunction "R_12") (pintype "passive"))
    )
    (net (code "120") (name "unconnected-(E16B-E-Pad10)") (class "Default")
      (node (ref "E16") (pin "10") (pinfunction "E_10") (pintype "output"))
    )
    (net (code "121") (name "unconnected-(E16B-R-Pad9)") (class "Default")
      (node (ref "E16") (pin "9") (pinfunction "R_9") (pintype "passive"))
    )
    (net (code "122") (name "unconnected-(E17A-~{Q}-Pad14)") (class "Default")
      (node (ref "E17") (pin "14") (pinfunction "~{Q}_14") (pintype "output"))
    )
    (net (code "123") (name "unconnected-(E18A-~{Q}-Pad14)") (class "Default")
      (node (ref "E18") (pin "14") (pinfunction "~{Q}_14") (pintype "output"))
    )
    (net (code "124") (name "unconnected-(E19B-~{Q}-Pad8)") (class "Default")
      (node (ref "E19") (pin "8") (pinfunction "~{Q}_8") (pintype "output"))
    )
    (net (code "125") (name "unconnected-(E20F-O-Pad7)") (class "Default")
      (node (ref "E20") (pin "7") (pinfunction "O_7") (pintype "output"))
    )
  )
)
